# ProPrj_RMwork_2025-11-14.net
KiCad netlist of a schematic drawn in EasyEDA Pro
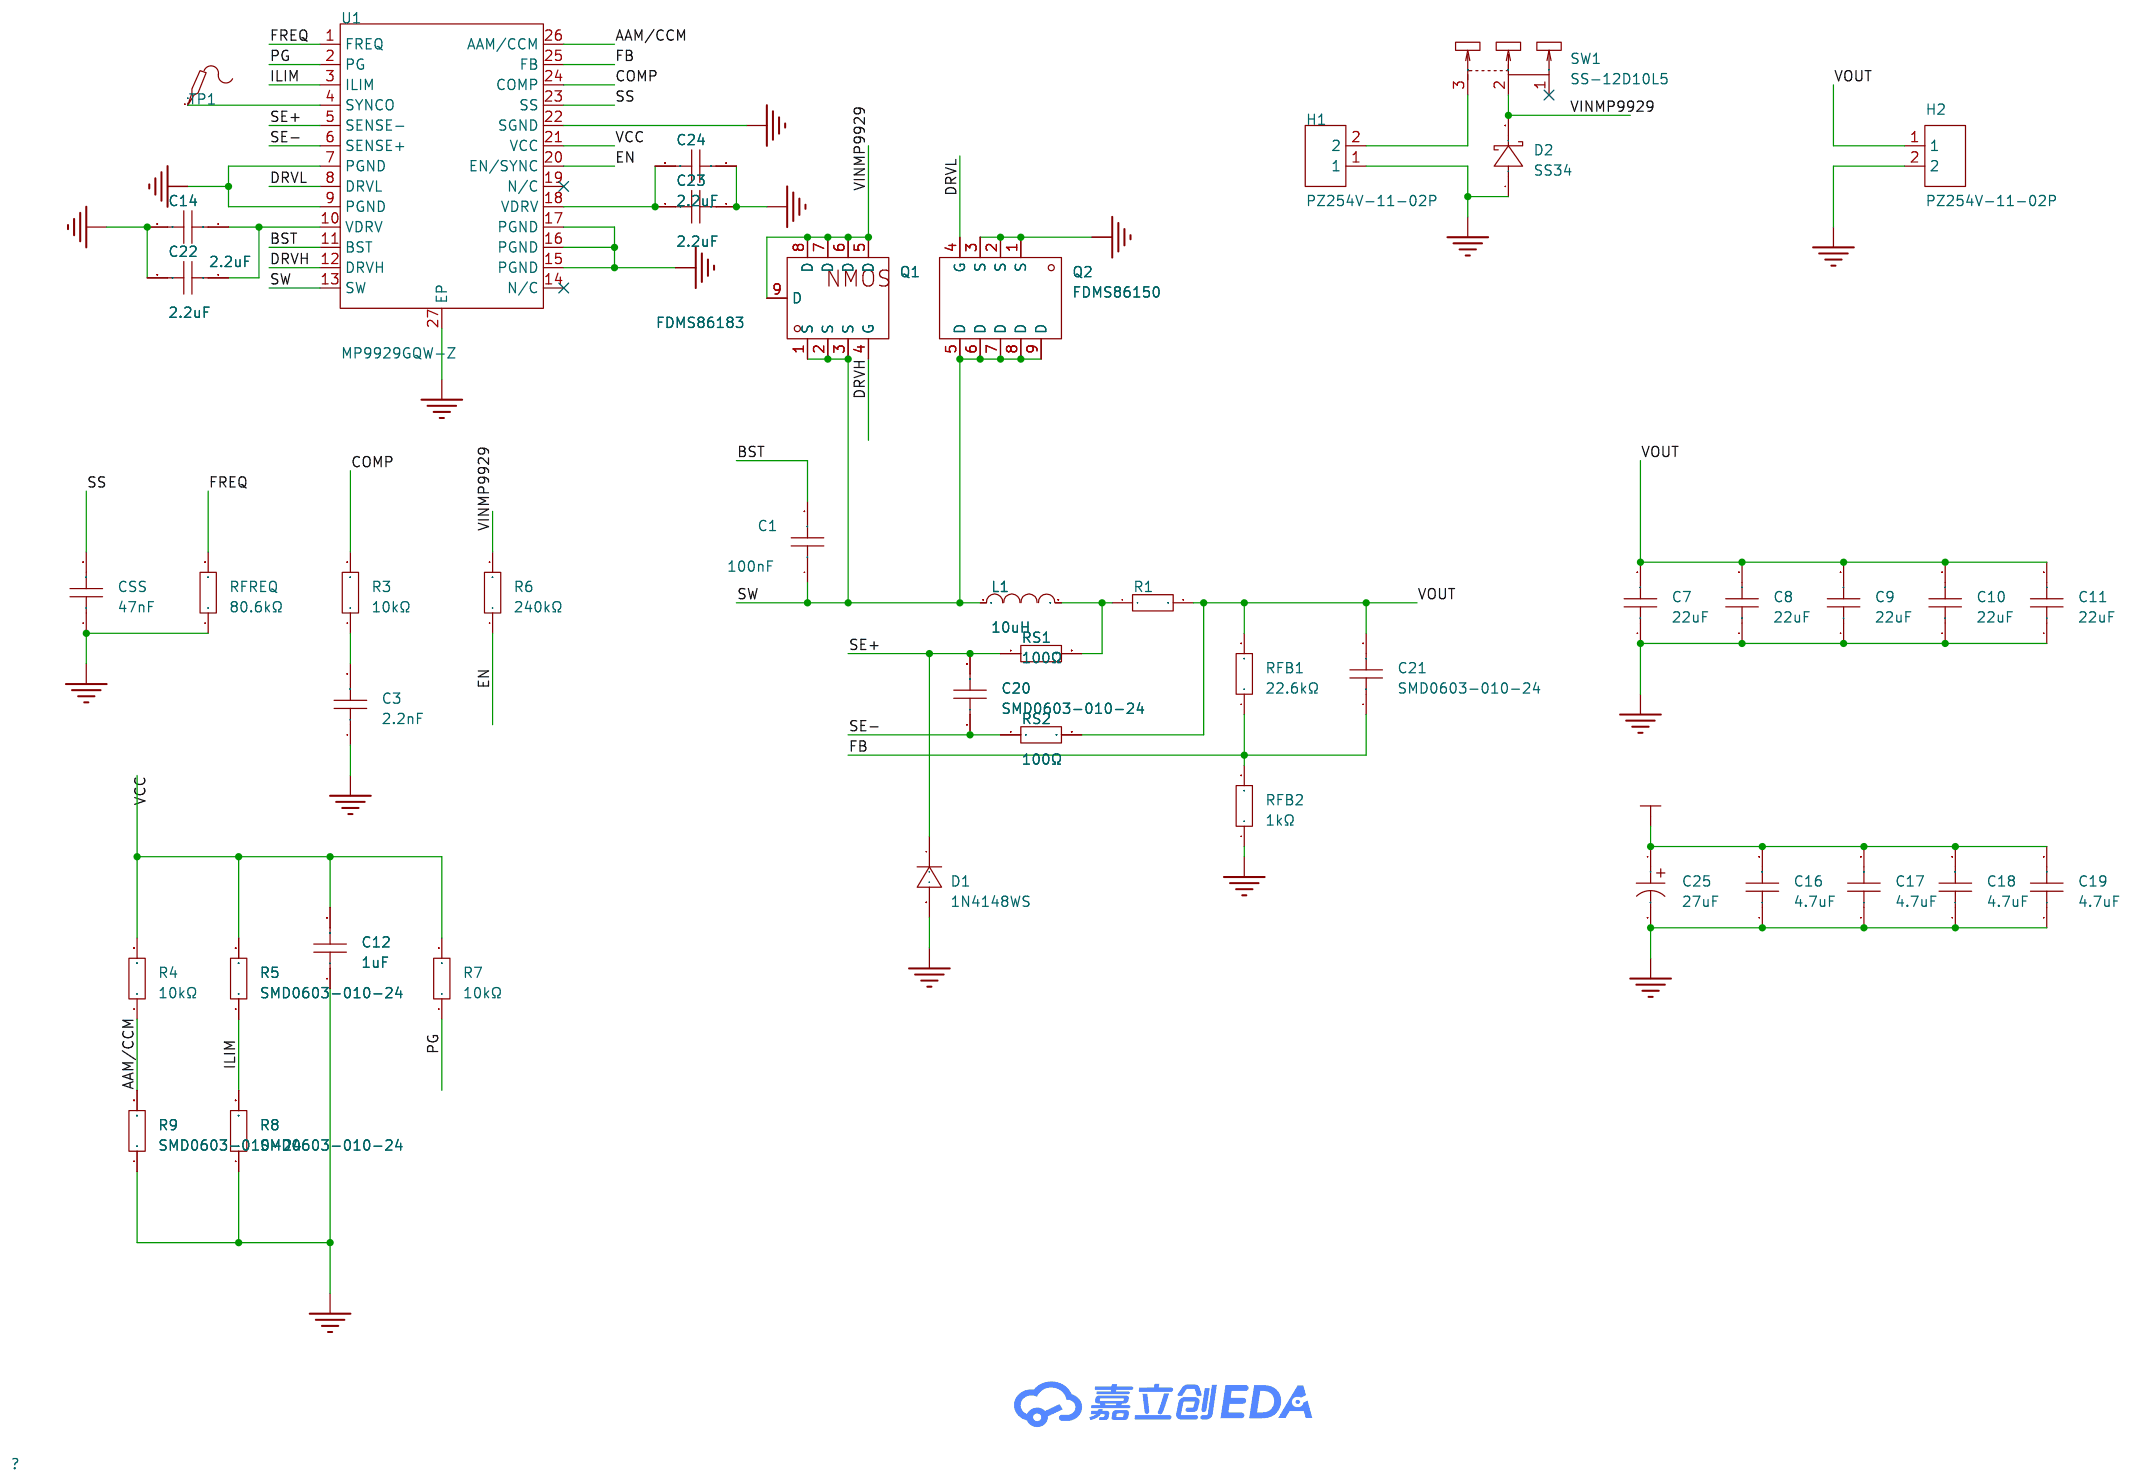
[diagram p0: schematic sheet]

(export (version "E")
  (design (tool "Eeschema 10.0.6"))
  (components
    (comp (ref "C1")
      (value "100nF")
      (footprint "easyedapro:C0603")
      (fields
        (field (name "Manufacturer Part") "CC0603KRX7R9BB104")
        (field (name "Manufacturer") "YAGEO(国巨)")
      )
      (libsource (lib "easyedapro") (part "Capacitance"))
    )
    (comp (ref "C3")
      (value "2.2nF")
      (footprint "easyedapro:C0603")
      (fields
        (field (name "Manufacturer Part") "FCC0603B222K500CT")
        (field (name "Manufacturer") "FOJAN(富捷)")
      )
      (libsource (lib "easyedapro") (part "Capacitance"))
    )
    (comp (ref "C7")
      (value "22uF")
      (footprint "easyedapro:C0603")
      (fields
        (field (name "Manufacturer Part") "CGA0603X5R226M160JT")
        (field (name "Manufacturer") "HRE(芯声)")
      )
      (libsource (lib "easyedapro") (part "Capacitance"))
    )
    (comp (ref "C8")
      (value "22uF")
      (footprint "easyedapro:C0603")
      (fields
        (field (name "Manufacturer Part") "CGA0603X5R226M160JT")
        (field (name "Manufacturer") "HRE(芯声)")
      )
      (libsource (lib "easyedapro") (part "Capacitance"))
    )
    (comp (ref "C9")
      (value "22uF")
      (footprint "easyedapro:C0603")
      (fields
        (field (name "Manufacturer Part") "CGA0603X5R226M160JT")
        (field (name "Manufacturer") "HRE(芯声)")
      )
      (libsource (lib "easyedapro") (part "Capacitance"))
    )
    (comp (ref "C10")
      (value "22uF")
      (footprint "easyedapro:C0603")
      (fields
        (field (name "Manufacturer Part") "CGA0603X5R226M160JT")
        (field (name "Manufacturer") "HRE(芯声)")
      )
      (libsource (lib "easyedapro") (part "Capacitance"))
    )
    (comp (ref "C11")
      (value "22uF")
      (footprint "easyedapro:C0603")
      (fields
        (field (name "Manufacturer Part") "CGA0603X5R226M160JT")
        (field (name "Manufacturer") "HRE(芯声)")
      )
      (libsource (lib "easyedapro") (part "Capacitance"))
    )
    (comp (ref "C12")
      (value "1uF")
      (footprint "easyedapro:C0603")
      (fields
        (field (name "Manufacturer Part") "CGA0603X5R105K160JT")
        (field (name "Manufacturer") "HRE(芯声)")
      )
      (libsource (lib "easyedapro") (part "Capacitance"))
    )
    (comp (ref "C14")
      (value "2.2uF")
      (footprint "easyedapro:C0603")
      (fields
        (field (name "Manufacturer Part") "CL10A225KA8NNNC")
        (field (name "Manufacturer") "SAMSUNG(三星)")
      )
      (libsource (lib "easyedapro") (part "Capacitance"))
    )
    (comp (ref "C16")
      (value "4.7uF")
      (footprint "easyedapro:C0603")
      (fields
        (field (name "Manufacturer Part") "CL10A475KO8NNNC")
        (field (name "Manufacturer") "SAMSUNG(三星)")
      )
      (libsource (lib "easyedapro") (part "Capacitance"))
    )
    (comp (ref "C17")
      (value "4.7uF")
      (footprint "easyedapro:C0603")
      (fields
        (field (name "Manufacturer Part") "CL10A475KO8NNNC")
        (field (name "Manufacturer") "SAMSUNG(三星)")
      )
      (libsource (lib "easyedapro") (part "Capacitance"))
    )
    (comp (ref "C18")
      (value "4.7uF")
      (footprint "easyedapro:C0603")
      (fields
        (field (name "Manufacturer Part") "CL10A475KO8NNNC")
        (field (name "Manufacturer") "SAMSUNG(三星)")
      )
      (libsource (lib "easyedapro") (part "Capacitance"))
    )
    (comp (ref "C19")
      (value "4.7uF")
      (footprint "easyedapro:C0603")
      (fields
        (field (name "Manufacturer Part") "CL10A475KO8NNNC")
        (field (name "Manufacturer") "SAMSUNG(三星)")
      )
      (libsource (lib "easyedapro") (part "Capacitance"))
    )
    (comp (ref "C20")
      (value "SMD0603-010-24")
      (footprint "easyedapro:C0603")
      (fields (field (name "Manufacturer") "R+O(宏嘉诚)"))
      (libsource (lib "easyedapro") (part "Capacitance"))
    )
    (comp (ref "C21")
      (value "SMD0603-010-24")
      (footprint "easyedapro:C0603")
      (fields (field (name "Manufacturer") "R+O(宏嘉诚)"))
      (libsource (lib "easyedapro") (part "Capacitance"))
    )
    (comp (ref "C22")
      (value "2.2uF")
      (footprint "easyedapro:C0603")
      (fields
        (field (name "Manufacturer Part") "CL10A225KA8NNNC")
        (field (name "Manufacturer") "SAMSUNG(三星)")
      )
      (libsource (lib "easyedapro") (part "Capacitance"))
    )
    (comp (ref "C23")
      (value "2.2uF")
      (footprint "easyedapro:C0603")
      (fields
        (field (name "Manufacturer Part") "CL10A225KA8NNNC")
        (field (name "Manufacturer") "SAMSUNG(三星)")
      )
      (libsource (lib "easyedapro") (part "Capacitance"))
    )
    (comp (ref "C24")
      (value "2.2uF")
      (footprint "easyedapro:C0603")
      (fields
        (field (name "Manufacturer Part") "CL10A225KA8NNNC")
        (field (name "Manufacturer") "SAMSUNG(三星)")
      )
      (libsource (lib "easyedapro") (part "Capacitance"))
    )
    (comp (ref "C25")
      (value "27uF")
      (footprint "easyedapro:CAP-TH_BD8.0-P3.50-D0.6-FD-H18.0")
      (description "容值:27uF;额定电压:400V;")
      (fields (field (name "Manufacturer Part") "25SVPF27MX") (field (name "Manufacturer") "PANASONIC(松下)"))
      (libsource (lib "easyedapro") (part "CD110276M2G0818VFL"))
    )
    (comp (ref "CSS")
      (value "47nF")
      (footprint "easyedapro:C0603")
      (fields
        (field (name "Manufacturer Part") "CL10B473KB8NNNC")
        (field (name "Manufacturer") "SAMSUNG(三星)")
      )
      (libsource (lib "easyedapro") (part "Capacitance"))
    )
    (comp (ref "D1")
      (value "1N4148WS")
      (footprint "easyedapro:SOD-323_L1.8-W1.3-LS2.5-RD")
      (description "二极管配置:独立式;正向压降(Vf):1.25V@150mA;直流反向耐压(Vr):100V;整流电流:150mA;反向恢复时间(Trr):4ns;")
      (fields (field (name "Manufacturer") "CJ(江苏长电/长晶)"))
      (libsource (lib "easyedapro") (part "1N4148WS T4"))
    )
    (comp (ref "D2")
      (value "SS34")
      (footprint "easyedapro:SMA_L4.3-W2.6-LS5.0-FD")
      (description "二极管配置:独立式;正向压降(Vf):550mV@3.0A;直流反向耐压(Vr):40V;整流电流:3A;")
      (fields (field (name "Manufacturer") "R+O(宏嘉诚)"))
      (libsource (lib "easyedapro") (part "SS34_C7420365"))
    )
    (comp (ref "H1")
      (value "PZ254V-11-02P")
      (footprint "easyedapro:HDR-TH_2P-P2.54-V-M")
      (fields (field (name "Manufacturer") "XFCN(兴飞)"))
      (libsource (lib "easyedapro") (part "PZ254V-11-02P"))
    )
    (comp (ref "H2")
      (value "PZ254V-11-02P")
      (footprint "easyedapro:HDR-TH_2P-P2.54-V-M")
      (fields (field (name "Manufacturer") "XFCN(兴飞)"))
      (libsource (lib "easyedapro") (part "PZ254V-11-02P"))
    )
    (comp (ref "L1")
      (value "10uH")
      (footprint "easyedapro:L0603")
      (fields (field (name "Manufacturer Part") "FXL1040-100-M") (field (name "Manufacturer") "cjiang(长江微电)"))
      (libsource (lib "easyedapro") (part "SDFL1608S100KTF"))
    )
    (comp (ref "Q1")
      (value "FDMS86183")
      (footprint "easyedapro:POWER-56_L5.0-W6.0-P1.27-LS6.2-BL")
      (description "类型:-;漏源电压(Vdss):-;连续漏极电流(Id):-;功率(Pd):-;导通电阻(RDS(on)@Vgs,Id):-;阈值电压(Vgs(th)@Id):-;")
      (fields (field (name "Manufacturer") "onsemi(安森美)"))
      (libsource (lib "easyedapro") (part "FDMS86183"))
    )
    (comp (ref "Q2")
      (value "FDMS86150")
      (footprint "easyedapro:POWER-56_L5.0-W6.0-P1.27-LS6.2-BL")
      (description "数量:1个N沟道;漏源电压(Vdss):100V;连续漏极电流(Id):80A;导通电阻(RDS(on)):7.8mΩ@6V,13A;耗散功率(Pd):156W;阈值电压(Vgs(th)):2V;")
      (fields (field (name "Manufacturer") "onsemi(安森美)"))
      (libsource (lib "easyedapro") (part "FDMS86150"))
    )
    (comp (ref "R1")
      (value "6mΩ")
      (footprint "easyedapro:R0603")
      (fields (field (name "Manufacturer Part") "RE2512F3R006") (field (name "Manufacturer") "JIERR(捷而瑞)"))
      (libsource (lib "easyedapro") (part "电阻"))
    )
    (comp (ref "R3")
      (value "10kΩ")
      (footprint "easyedapro:R0603")
      (fields
        (field (name "Manufacturer Part") "0603WAF1002T5E")
        (field (name "Manufacturer") "UNI-ROYAL(厚声)")
      )
      (libsource (lib "easyedapro") (part "电阻"))
    )
    (comp (ref "R4")
      (value "10kΩ")
      (footprint "easyedapro:R0603")
      (fields
        (field (name "Manufacturer Part") "0603WAF1002T5E")
        (field (name "Manufacturer") "UNI-ROYAL(厚声)")
      )
      (libsource (lib "easyedapro") (part "电阻"))
    )
    (comp (ref "R5")
      (value "SMD0603-010-24")
      (footprint "easyedapro:R0603")
      (fields (field (name "Manufacturer") "R+O(宏嘉诚)"))
      (libsource (lib "easyedapro") (part "电阻"))
    )
    (comp (ref "R6")
      (value "240kΩ")
      (footprint "easyedapro:R0603")
      (fields
        (field (name "Manufacturer Part") "0603WAF2403T5E")
        (field (name "Manufacturer") "UNI-ROYAL(厚声)")
      )
      (libsource (lib "easyedapro") (part "电阻"))
    )
    (comp (ref "R7")
      (value "10kΩ")
      (footprint "easyedapro:R0603")
      (fields
        (field (name "Manufacturer Part") "0603WAF1002T5E")
        (field (name "Manufacturer") "UNI-ROYAL(厚声)")
      )
      (libsource (lib "easyedapro") (part "电阻"))
    )
    (comp (ref "R8")
      (value "SMD0603-010-24")
      (footprint "easyedapro:R0603")
      (fields (field (name "Manufacturer") "R+O(宏嘉诚)"))
      (libsource (lib "easyedapro") (part "电阻"))
    )
    (comp (ref "R9")
      (value "SMD0603-010-24")
      (footprint "easyedapro:R0603")
      (fields (field (name "Manufacturer") "R+O(宏嘉诚)"))
      (libsource (lib "easyedapro") (part "电阻"))
    )
    (comp (ref "RFB1")
      (value "22.6kΩ")
      (footprint "easyedapro:R0603")
      (fields (field (name "Manufacturer Part") "PTFR0603B22K6N9") (field (name "Manufacturer") "RESI(开步睿思)"))
      (libsource (lib "easyedapro") (part "电阻"))
    )
    (comp (ref "RFB2")
      (value "1kΩ")
      (footprint "easyedapro:R0603")
      (fields (field (name "Manufacturer Part") "FRC0603F1001TS") (field (name "Manufacturer") "FOJAN(富捷)"))
      (libsource (lib "easyedapro") (part "电阻"))
    )
    (comp (ref "RFREQ")
      (value "80.6kΩ")
      (footprint "easyedapro:R0603")
      (fields (field (name "Manufacturer Part") "FRC0603F8062TS") (field (name "Manufacturer") "FOJAN(富捷)"))
      (libsource (lib "easyedapro") (part "电阻"))
    )
    (comp (ref "RS1")
      (value "100Ω")
      (footprint "easyedapro:R0603")
      (fields
        (field (name "Manufacturer Part") "0603WAF1000T5E")
        (field (name "Manufacturer") "UNI-ROYAL(厚声)")
      )
      (libsource (lib "easyedapro") (part "电阻"))
    )
    (comp (ref "RS2")
      (value "100Ω")
      (footprint "easyedapro:R0603")
      (fields
        (field (name "Manufacturer Part") "0603WAF1000T5E")
        (field (name "Manufacturer") "UNI-ROYAL(厚声)")
      )
      (libsource (lib "easyedapro") (part "电阻"))
    )
    (comp (ref "SW1")
      (value "SS-12D10L5")
      (footprint "easyedapro:SW-TH_SS-12D10L5")
      (description "电路结构:单刀双掷;安装方式:直插;开关颜色:黑色;额定电流:3A;额定电压:125V;工作寿命:1万次;")
      (fields (field (name "Manufacturer") "XKB Connection(中国星坤)"))
      (libsource (lib "easyedapro") (part "SS-12D10L5"))
    )
    (comp (ref "TP1")
      (value "~")
      (footprint "easyedapro:Test-Point-0.5mm")
      (description "Test Point 测试点")
      (libsource (lib "easyedapro") (part "Test-Point"))
    )
    (comp (ref "U1")
      (value "MP9929GQW-Z")
      (footprint "easyedapro:QFN-26_L6.0-W4.0-P0.50_MP9929GQW-Z")
      (fields (field (name "Manufacturer") "MPS(芯源)"))
      (libsource (lib "easyedapro") (part "MP9929GQW-Z"))
    )
  )
  (nets
    (net (code "1") (name "/AAM{slash}CCM") (class "Default")
      (node (ref "R4") (pin "1") (pinfunction "1_1") (pintype "input"))
      (node (ref "R9") (pin "2") (pinfunction "2_2") (pintype "input"))
      (node (ref "U1") (pin "26") (pinfunction "AAM/CCM_26") (pintype "unspecified"))
    )
    (net (code "2") (name "/BST") (class "Default")
      (node (ref "C1") (pin "2") (pinfunction "2_2") (pintype "input"))
      (node (ref "U1") (pin "11") (pinfunction "BST_11") (pintype "unspecified"))
    )
    (net (code "3") (name "/COMP") (class "Default")
      (node (ref "R3") (pin "2") (pinfunction "2_2") (pintype "input"))
      (node (ref "U1") (pin "24") (pinfunction "COMP_24") (pintype "unspecified"))
    )
    (net (code "4") (name "/DRVH") (class "Default")
      (node (ref "Q1") (pin "4") (pinfunction "G_4") (pintype "unspecified"))
      (node (ref "U1") (pin "12") (pinfunction "DRVH_12") (pintype "unspecified"))
    )
    (net (code "5") (name "/DRVL") (class "Default")
      (node (ref "Q2") (pin "4") (pinfunction "G_4") (pintype "unspecified"))
      (node (ref "U1") (pin "8") (pinfunction "DRVL_8") (pintype "unspecified"))
    )
    (net (code "6") (name "/EN") (class "Default")
      (node (ref "R6") (pin "1") (pinfunction "1_1") (pintype "input"))
      (node (ref "U1") (pin "20") (pinfunction "EN/SYNC_20") (pintype "unspecified"))
    )
    (net (code "7") (name "/FB") (class "Default")
      (node (ref "C21") (pin "1") (pinfunction "1_1") (pintype "input"))
      (node (ref "RFB1") (pin "1") (pinfunction "1_1") (pintype "input"))
      (node (ref "RFB2") (pin "2") (pinfunction "2_2") (pintype "input"))
      (node (ref "U1") (pin "25") (pinfunction "FB_25") (pintype "unspecified"))
    )
    (net (code "8") (name "/FREQ") (class "Default")
      (node (ref "RFREQ") (pin "2") (pinfunction "2_2") (pintype "input"))
      (node (ref "U1") (pin "1") (pinfunction "FREQ_1") (pintype "unspecified"))
    )
    (net (code "9") (name "/ILIM") (class "Default")
      (node (ref "R5") (pin "1") (pinfunction "1_1") (pintype "input"))
      (node (ref "R8") (pin "2") (pinfunction "2_2") (pintype "input"))
      (node (ref "U1") (pin "3") (pinfunction "ILIM_3") (pintype "unspecified"))
    )
    (net (code "10") (name "/PG") (class "Default")
      (node (ref "R7") (pin "1") (pinfunction "1_1") (pintype "input"))
      (node (ref "U1") (pin "2") (pinfunction "PG_2") (pintype "unspecified"))
    )
    (net (code "11") (name "/SE+") (class "Default")
      (node (ref "C20") (pin "2") (pinfunction "2_2") (pintype "input"))
      (node (ref "D1") (pin "1") (pinfunction "K_1") (pintype "unspecified"))
      (node (ref "RS1") (pin "1") (pinfunction "1_1") (pintype "input"))
      (node (ref "U1") (pin "5") (pinfunction "SENSE-_5") (pintype "unspecified"))
    )
    (net (code "12") (name "/SE-") (class "Default")
      (node (ref "C20") (pin "1") (pinfunction "1_1") (pintype "input"))
      (node (ref "RS2") (pin "1") (pinfunction "1_1") (pintype "input"))
      (node (ref "U1") (pin "6") (pinfunction "SENSE+_6") (pintype "unspecified"))
    )
    (net (code "13") (name "/SS") (class "Default")
      (node (ref "CSS") (pin "2") (pinfunction "2_2") (pintype "input"))
      (node (ref "U1") (pin "23") (pinfunction "SS_23") (pintype "unspecified"))
    )
    (net (code "14") (name "/SW") (class "Default")
      (node (ref "C1") (pin "1") (pinfunction "1_1") (pintype "input"))
      (node (ref "L1") (pin "1") (pinfunction "1_1") (pintype "unspecified"))
      (node (ref "Q1") (pin "1") (pinfunction "S_1") (pintype "unspecified"))
      (node (ref "Q1") (pin "2") (pinfunction "S_2") (pintype "unspecified"))
      (node (ref "Q1") (pin "3") (pinfunction "S_3") (pintype "unspecified"))
      (node (ref "Q2") (pin "5") (pinfunction "D_5") (pintype "unspecified"))
      (node (ref "Q2") (pin "6") (pinfunction "D_6") (pintype "unspecified"))
      (node (ref "Q2") (pin "7") (pinfunction "D_7") (pintype "unspecified"))
      (node (ref "Q2") (pin "8") (pinfunction "D_8") (pintype "unspecified"))
      (node (ref "Q2") (pin "9") (pinfunction "D_9") (pintype "unspecified"))
      (node (ref "U1") (pin "13") (pinfunction "SW_13") (pintype "unspecified"))
    )
    (net (code "15") (name "/VCC") (class "Default")
      (node (ref "C12") (pin "2") (pinfunction "2_2") (pintype "input"))
      (node (ref "R4") (pin "2") (pinfunction "2_2") (pintype "input"))
      (node (ref "R5") (pin "2") (pinfunction "2_2") (pintype "input"))
      (node (ref "R7") (pin "2") (pinfunction "2_2") (pintype "input"))
      (node (ref "U1") (pin "21") (pinfunction "VCC_21") (pintype "unspecified"))
    )
    (net (code "16") (name "/VOUT") (class "Default")
      (node (ref "C10") (pin "2") (pinfunction "2_2") (pintype "input"))
      (node (ref "C11") (pin "2") (pinfunction "2_2") (pintype "input"))
      (node (ref "C21") (pin "2") (pinfunction "2_2") (pintype "input"))
      (node (ref "C7") (pin "2") (pinfunction "2_2") (pintype "input"))
      (node (ref "C8") (pin "2") (pinfunction "2_2") (pintype "input"))
      (node (ref "C9") (pin "2") (pinfunction "2_2") (pintype "input"))
      (node (ref "H2") (pin "1") (pinfunction "1_1") (pintype "unspecified"))
      (node (ref "R1") (pin "2") (pinfunction "2_2") (pintype "input"))
      (node (ref "RFB1") (pin "2") (pinfunction "2_2") (pintype "input"))
      (node (ref "RS2") (pin "2") (pinfunction "2_2") (pintype "input"))
    )
    (net (code "17") (name "GND") (class "Default")
      (node (ref "C10") (pin "1") (pinfunction "1_1") (pintype "input"))
      (node (ref "C11") (pin "1") (pinfunction "1_1") (pintype "input"))
      (node (ref "C12") (pin "1") (pinfunction "1_1") (pintype "input"))
      (node (ref "C14") (pin "2") (pinfunction "2_2") (pintype "input"))
      (node (ref "C16") (pin "1") (pinfunction "1_1") (pintype "input"))
      (node (ref "C17") (pin "1") (pinfunction "1_1") (pintype "input"))
      (node (ref "C18") (pin "1") (pinfunction "1_1") (pintype "input"))
      (node (ref "C19") (pin "1") (pinfunction "1_1") (pintype "input"))
      (node (ref "C22") (pin "2") (pinfunction "2_2") (pintype "input"))
      (node (ref "C23") (pin "1") (pinfunction "1_1") (pintype "input"))
      (node (ref "C24") (pin "1") (pinfunction "1_1") (pintype "input"))
      (node (ref "C25") (pin "2") (pinfunction "2_2") (pintype "input"))
      (node (ref "C3") (pin "1") (pinfunction "1_1") (pintype "input"))
      (node (ref "C7") (pin "1") (pinfunction "1_1") (pintype "input"))
      (node (ref "C8") (pin "1") (pinfunction "1_1") (pintype "input"))
      (node (ref "C9") (pin "1") (pinfunction "1_1") (pintype "input"))
      (node (ref "CSS") (pin "1") (pinfunction "1_1") (pintype "input"))
      (node (ref "D1") (pin "2") (pinfunction "A_2") (pintype "unspecified"))
      (node (ref "D2") (pin "1") (pinfunction "A_1") (pintype "unspecified"))
      (node (ref "H1") (pin "1") (pinfunction "1_1") (pintype "unspecified"))
      (node (ref "H2") (pin "2") (pinfunction "2_2") (pintype "unspecified"))
      (node (ref "Q2") (pin "1") (pinfunction "S_1") (pintype "unspecified"))
      (node (ref "Q2") (pin "2") (pinfunction "S_2") (pintype "unspecified"))
      (node (ref "Q2") (pin "3") (pinfunction "S_3") (pintype "unspecified"))
      (node (ref "R8") (pin "1") (pinfunction "1_1") (pintype "input"))
      (node (ref "R9") (pin "1") (pinfunction "1_1") (pintype "input"))
      (node (ref "RFB2") (pin "1") (pinfunction "1_1") (pintype "input"))
      (node (ref "RFREQ") (pin "1") (pinfunction "1_1") (pintype "input"))
      (node (ref "U1") (pin "15") (pinfunction "PGND_15") (pintype "unspecified"))
      (node (ref "U1") (pin "16") (pinfunction "PGND_16") (pintype "unspecified"))
      (node (ref "U1") (pin "17") (pinfunction "PGND_17") (pintype "unspecified"))
      (node (ref "U1") (pin "22") (pinfunction "SGND_22") (pintype "unspecified"))
      (node (ref "U1") (pin "27") (pinfunction "EP_27") (pintype "unspecified"))
      (node (ref "U1") (pin "7") (pinfunction "PGND_7") (pintype "unspecified"))
      (node (ref "U1") (pin "9") (pinfunction "PGND_9") (pintype "unspecified"))
    )
    (net (code "18") (name "Net-(C3-Pad2)") (class "Default")
      (node (ref "C3") (pin "2") (pinfunction "2_2") (pintype "input"))
      (node (ref "R3") (pin "1") (pinfunction "1_1") (pintype "input"))
    )
    (net (code "19") (name "Net-(C14-Pad1)") (class "Default")
      (node (ref "C14") (pin "1") (pinfunction "1_1") (pintype "input"))
      (node (ref "C22") (pin "1") (pinfunction "1_1") (pintype "input"))
      (node (ref "U1") (pin "10") (pinfunction "VDRV_10") (pintype "unspecified"))
    )
    (net (code "20") (name "Net-(C23-Pad2)") (class "Default")
      (node (ref "C23") (pin "2") (pinfunction "2_2") (pintype "input"))
      (node (ref "C24") (pin "2") (pinfunction "2_2") (pintype "input"))
      (node (ref "U1") (pin "18") (pinfunction "VDRV_18") (pintype "unspecified"))
    )
    (net (code "21") (name "Net-(H1-Pad2)") (class "Default")
      (node (ref "H1") (pin "2") (pinfunction "2_2") (pintype "unspecified"))
      (node (ref "SW1") (pin "3") (pinfunction "3_3") (pintype "unspecified"))
    )
    (net (code "22") (name "Net-(L1-Pad2)") (class "Default")
      (node (ref "L1") (pin "2") (pinfunction "2_2") (pintype "unspecified"))
      (node (ref "R1") (pin "1") (pinfunction "1_1") (pintype "input"))
      (node (ref "RS1") (pin "2") (pinfunction "2_2") (pintype "input"))
    )
    (net (code "23") (name "Net-(U1-SYNCO)") (class "Default")
      (node (ref "TP1") (pin "1") (pinfunction "1_1") (pintype "input"))
      (node (ref "U1") (pin "4") (pinfunction "SYNCO_4") (pintype "unspecified"))
    )
    (net (code "24") (name "VINMP9929") (class "Default")
      (node (ref "C16") (pin "2") (pinfunction "2_2") (pintype "input"))
      (node (ref "C17") (pin "2") (pinfunction "2_2") (pintype "input"))
      (node (ref "C18") (pin "2") (pinfunction "2_2") (pintype "input"))
      (node (ref "C19") (pin "2") (pinfunction "2_2") (pintype "input"))
      (node (ref "C25") (pin "1") (pinfunction "1_1") (pintype "input"))
      (node (ref "D2") (pin "2") (pinfunction "K_2") (pintype "unspecified"))
      (node (ref "Q1") (pin "5") (pinfunction "D_5") (pintype "unspecified"))
      (node (ref "Q1") (pin "6") (pinfunction "D_6") (pintype "unspecified"))
      (node (ref "Q1") (pin "7") (pinfunction "D_7") (pintype "unspecified"))
      (node (ref "Q1") (pin "8") (pinfunction "D_8") (pintype "unspecified"))
      (node (ref "Q1") (pin "9") (pinfunction "D_9") (pintype "unspecified"))
      (node (ref "R6") (pin "2") (pinfunction "2_2") (pintype "input"))
      (node (ref "SW1") (pin "2") (pinfunction "2_2") (pintype "unspecified"))
    )
    (net (code "25") (name "unconnected-(SW1-Pad1)") (class "Default")
      (node (ref "SW1") (pin "1") (pinfunction "1_1") (pintype "unspecified+no_connect"))
    )
    (net (code "26") (name "unconnected-(U1-N{slash}C-Pad14)") (class "Default")
      (node (ref "U1") (pin "14") (pinfunction "N/C_14") (pintype "unspecified+no_connect"))
    )
    (net (code "27") (name "unconnected-(U1-N{slash}C-Pad19)") (class "Default")
      (node (ref "U1") (pin "19") (pinfunction "N/C_19") (pintype "unspecified+no_connect"))
    )
  )
)
